# Potentiometer.net
KiCad netlist of a schematic drawn in Altium Designer
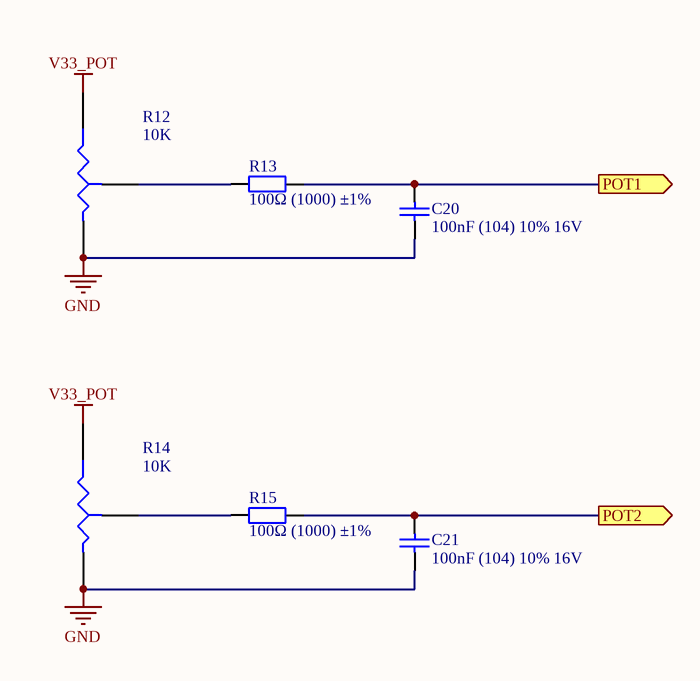
[diagram p0: Potentiometer.SchDoc]

(export (version "E")
  (design (tool "Eeschema 10.0.6"))
  (components
    (comp (ref "C20")
      (value "100nF (104) 10% 16V")
      (footprint "0402_C")
      (description "贴片电容")
      (libsource (lib "Miscellaneous Devices LC") (part "0402 100nF (104) 10% 16V"))
    )
    (comp (ref "C21")
      (value "100nF (104) 10% 16V")
      (footprint "0402_C")
      (description "贴片电容")
      (libsource (lib "Miscellaneous Devices LC") (part "0402 100nF (104) 10% 16V"))
    )
    (comp (ref "R12")
      (value "10K")
      (footprint "AIN16")
      (description "Tapped Resistor")
      (fields (field (name "PUBLISHER") "Altium Limited"))
      (libsource (lib "Miscellaneous Devices") (part "Res Tap"))
    )
    (comp (ref "R13")
      (value "100Ω (1000) ±1%")
      (footprint "0402_R")
      (description "贴片电阻")
      (libsource (lib "Miscellaneous Devices LC") (part "0402 100Ω (1000) 1%"))
    )
    (comp (ref "R14")
      (value "10K")
      (footprint "AIN16")
      (description "Tapped Resistor")
      (fields (field (name "PUBLISHER") "Altium Limited"))
      (libsource (lib "Miscellaneous Devices") (part "Res Tap"))
    )
    (comp (ref "R15")
      (value "100Ω (1000) ±1%")
      (footprint "0402_R")
      (description "贴片电阻")
      (libsource (lib "Miscellaneous Devices LC") (part "0402 100Ω (1000) 1%"))
    )
  )
  (nets
    (net (code "1") (name "/POT1") (class "Default")
      (node (ref "C20") (pin "2") (pinfunction "2_2") (pintype "passive"))
      (node (ref "R13") (pin "2") (pinfunction "2_2") (pintype "passive"))
    )
    (net (code "2") (name "/POT2") (class "Default")
      (node (ref "C21") (pin "2") (pinfunction "2_2") (pintype "passive"))
      (node (ref "R15") (pin "2") (pinfunction "2_2") (pintype "passive"))
    )
    (net (code "3") (name "GND") (class "Default")
      (node (ref "C20") (pin "1") (pinfunction "1_1") (pintype "passive"))
      (node (ref "C21") (pin "1") (pinfunction "1_1") (pintype "passive"))
      (node (ref "R12") (pin "1") (pinfunction "A_1") (pintype "passive"))
      (node (ref "R14") (pin "1") (pinfunction "A_1") (pintype "passive"))
    )
    (net (code "4") (name "Net-(R12-TAP)") (class "Default")
      (node (ref "R12") (pin "3") (pinfunction "TAP_3") (pintype "passive"))
      (node (ref "R13") (pin "1") (pinfunction "1_1") (pintype "passive"))
    )
    (net (code "5") (name "Net-(R14-TAP)") (class "Default")
      (node (ref "R14") (pin "3") (pinfunction "TAP_3") (pintype "passive"))
      (node (ref "R15") (pin "1") (pinfunction "1_1") (pintype "passive"))
    )
    (net (code "6") (name "V33_POT") (class "Default")
      (node (ref "R12") (pin "2") (pinfunction "B_2") (pintype "passive"))
      (node (ref "R14") (pin "2") (pinfunction "B_2") (pintype "passive"))
    )
  )
)
